# digital_voltage_channel.net
KiCad netlist of a schematic drawn in Altium Designer
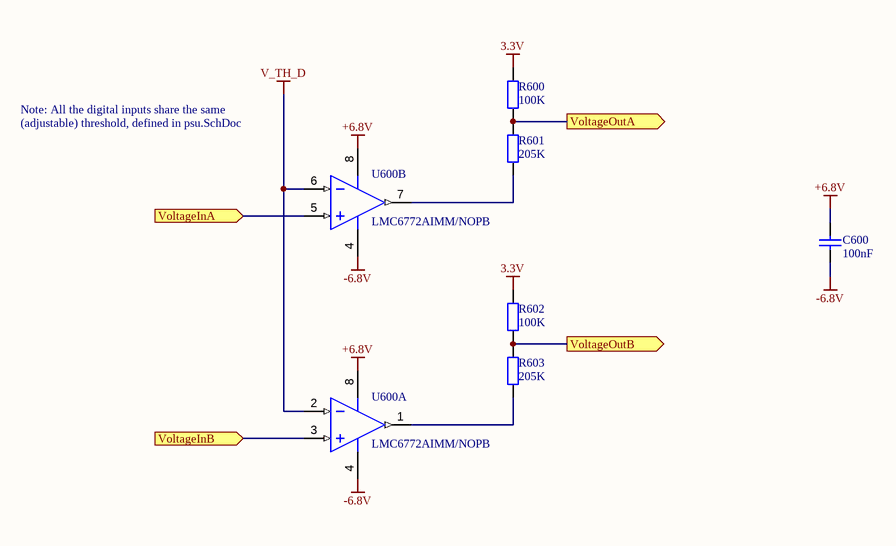
[diagram p0: digital_voltage_channel.SchDoc]

(export (version "E")
  (design (tool "Eeschema 10.0.6"))
  (components
    (comp (ref "C600")
      (value "100nF")
      (footprint "CAPC0402(1005)60_L")
      (description "CAP 100nF 16V -20% to +80% 0402 (1005 Metric) Thickness 0.6mm SMD")
      (fields (field (name "TOLERANCE") "-20% to +80%"))
      (libsource (lib "Altium Content Vault") (part "CMP-1034-02071-1"))
    )
    (comp (ref "R600")
      (value "100K")
      (footprint "RESC0402(1005)_L")
      (description "100K 0.063W 1% 0402 (1005 Metric)  SMD")
      (fields (field (name "TOLERANCE") "1 %") (field (name "POWER") "0.063 W"))
      (libsource (lib "Altium Content Vault") (part "CMP-1011-00801-1"))
    )
    (comp (ref "R601")
      (value "205K")
      (footprint "RESC0402(1005)_L")
      (description "205K 0.063W 1% 0402 (1005 Metric)  SMD")
      (fields (field (name "TOLERANCE") "1 %") (field (name "POWER") "0.063 W"))
      (libsource (lib "Altium Content Vault") (part "CMP-1011-00769-1"))
    )
    (comp (ref "R602")
      (value "100K")
      (footprint "RESC0402(1005)_L")
      (description "100K 0.063W 1% 0402 (1005 Metric)  SMD")
      (fields (field (name "TOLERANCE") "1 %") (field (name "POWER") "0.063 W"))
      (libsource (lib "Altium Content Vault") (part "CMP-1011-00801-1"))
    )
    (comp (ref "R603")
      (value "205K")
      (footprint "RESC0402(1005)_L")
      (description "205K 0.063W 1% 0402 (1005 Metric)  SMD")
      (fields (field (name "TOLERANCE") "1 %") (field (name "POWER") "0.063 W"))
      (libsource (lib "Altium Content Vault") (part "CMP-1011-00769-1"))
    )
    (comp (ref "U600")
      (value "LMC6772AIMM/NOPB")
      (footprint "DGK0008A_L")
      (fields (field (name "MANUFACTURER") "Texas Instruments"))
      (libsource (lib "Altium Content Vault") (part "AN-COMP-LMC6762-8"))
    )
  )
  (nets
    (net (code "1") (name "+6.8V") (class "Default")
      (node (ref "C600") (pin "2") (pinfunction "2_2") (pintype "passive"))
      (node (ref "U600") (pin "8") (pinfunction "V+_8") (pintype "power_in"))
    )
    (net (code "2") (name "-6.8V") (class "Default")
      (node (ref "C600") (pin "1") (pinfunction "1_1") (pintype "passive"))
      (node (ref "U600") (pin "4") (pinfunction "V-_4") (pintype "power_in"))
    )
    (net (code "3") (name "/VoltageInA") (class "Default")
      (node (ref "U600") (pin "5") (pinfunction "INB+_5") (pintype "input"))
    )
    (net (code "4") (name "/VoltageInB") (class "Default")
      (node (ref "U600") (pin "3") (pinfunction "INA+_3") (pintype "input"))
    )
    (net (code "5") (name "/VoltageOutA") (class "Default")
      (node (ref "R600") (pin "1") (pinfunction "1_1") (pintype "passive"))
      (node (ref "R601") (pin "2") (pinfunction "2_2") (pintype "passive"))
    )
    (net (code "6") (name "/VoltageOutB") (class "Default")
      (node (ref "R602") (pin "1") (pinfunction "1_1") (pintype "passive"))
      (node (ref "R603") (pin "2") (pinfunction "2_2") (pintype "passive"))
    )
    (net (code "7") (name "3.3V") (class "Default")
      (node (ref "R600") (pin "2") (pinfunction "2_2") (pintype "passive"))
      (node (ref "R602") (pin "2") (pinfunction "2_2") (pintype "passive"))
    )
    (net (code "8") (name "Net-(U600A-OUTA)") (class "Default")
      (node (ref "R603") (pin "1") (pinfunction "1_1") (pintype "passive"))
      (node (ref "U600") (pin "1") (pinfunction "OUTA_1") (pintype "output"))
    )
    (net (code "9") (name "Net-(U600B-OUTB)") (class "Default")
      (node (ref "R601") (pin "1") (pinfunction "1_1") (pintype "passive"))
      (node (ref "U600") (pin "7") (pinfunction "OUTB_7") (pintype "output"))
    )
    (net (code "10") (name "V_TH_D") (class "Default")
      (node (ref "U600") (pin "2") (pinfunction "INA-_2") (pintype "input"))
      (node (ref "U600") (pin "6") (pinfunction "INB-_6") (pintype "input"))
    )
  )
)
